# Heartmonitor_schem_EasyEDA.net
KiCad netlist of a schematic drawn in EasyEDA
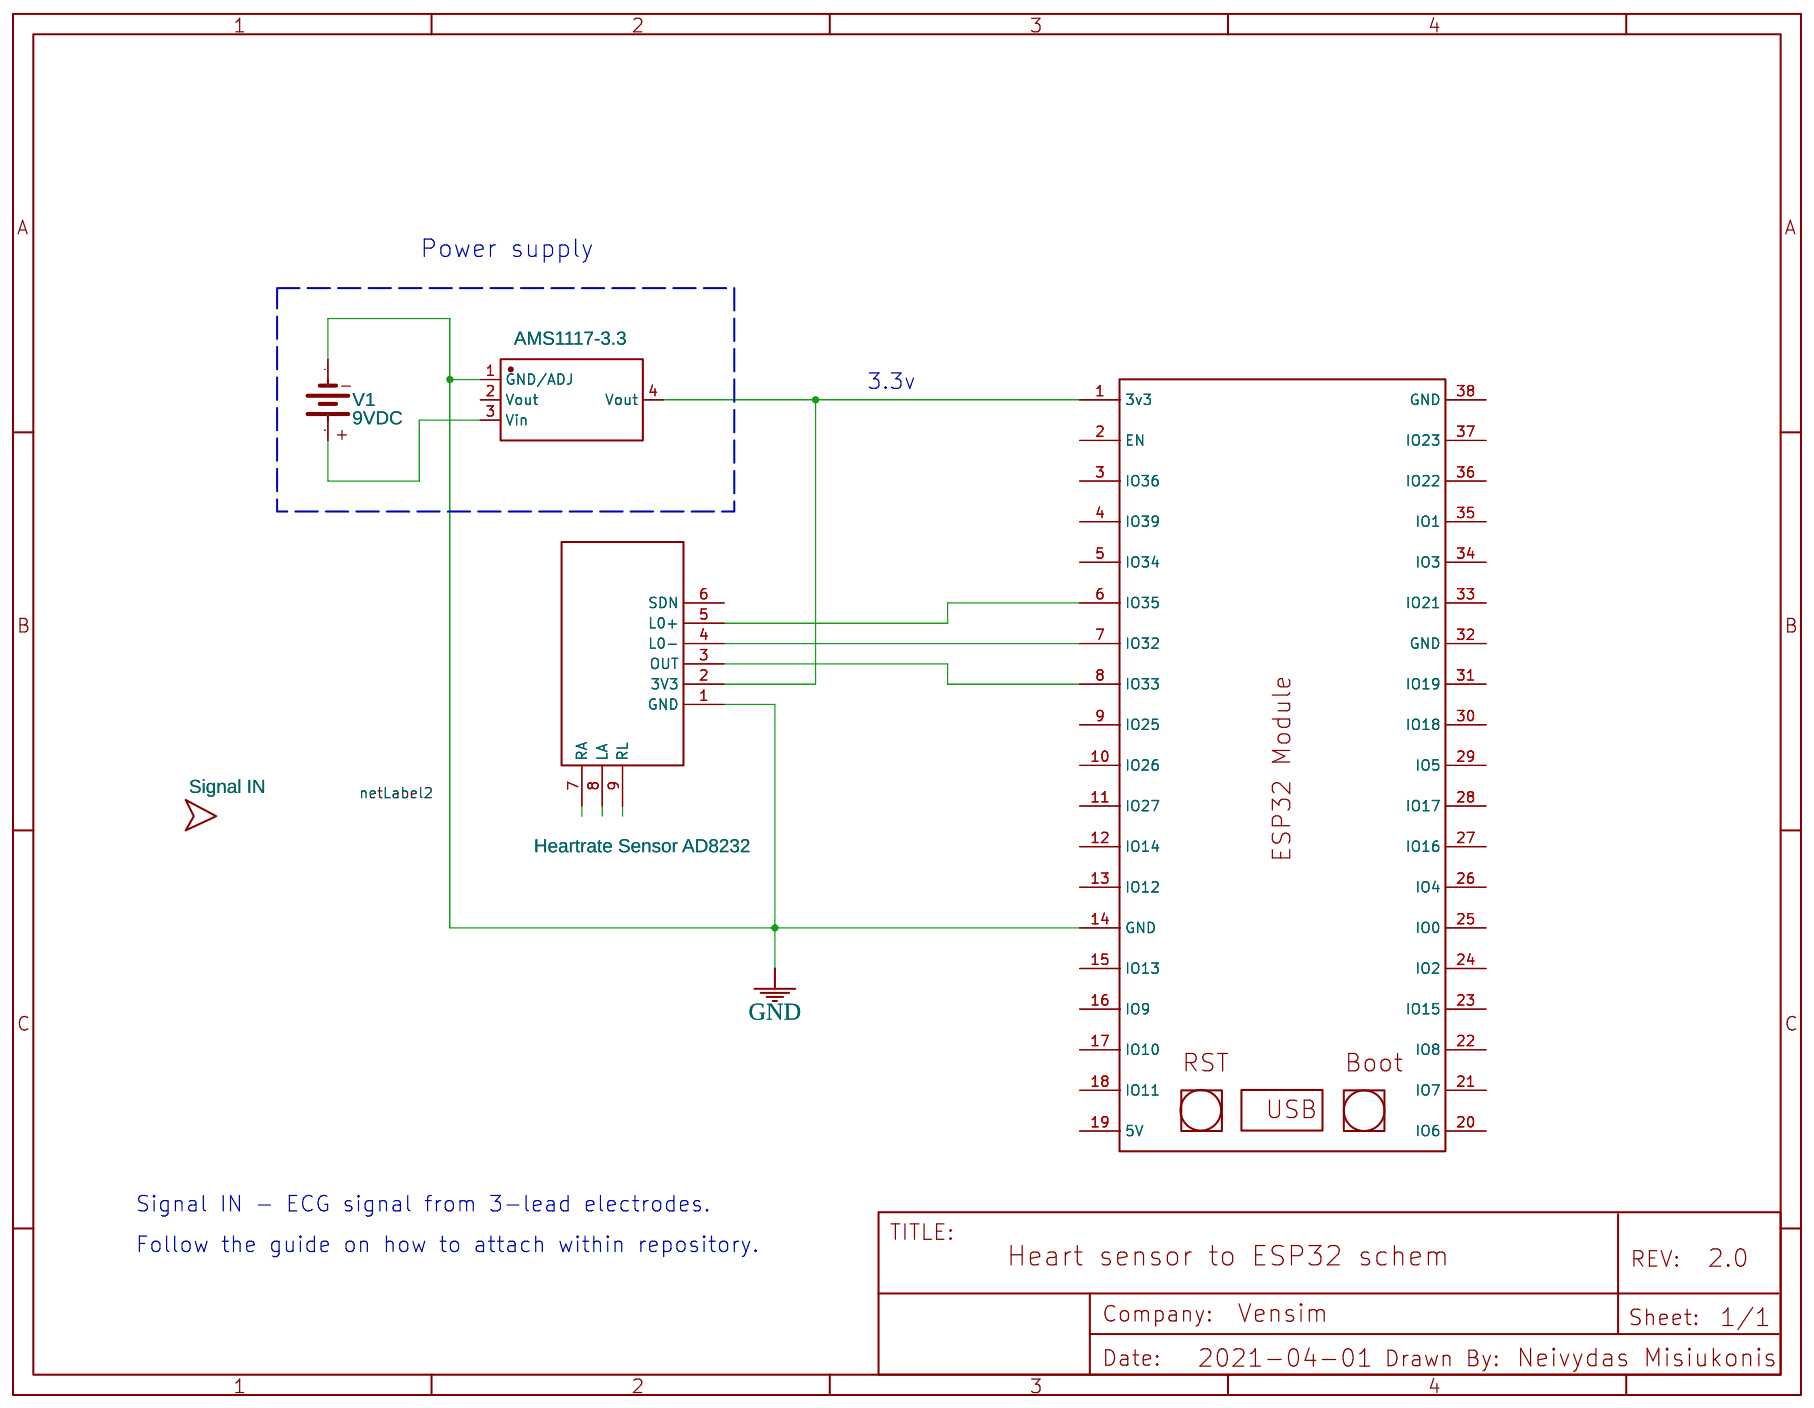
[diagram p0: schematic sheet]

(export (version "E")
  (design (tool "Eeschema 10.0.6"))
  (components
    (comp (ref "U1") (value "Heartrate Sensor AD8232") (libsource (lib "") (part "Heartrate Sensor AD8232")))
    (comp (ref "U2")
      (value "ESP32 BLADE")
      (fields (field (name "BOM_Manufacturer Part") "ESP32"))
      (libsource (lib "") (part "ESP32 BLADE"))
    )
    (comp (ref "U3")
      (value "AMS1117-3.3")
      (fields (field (name "BOM_Supplier Part") "C6186"))
      (libsource (lib "") (part "AMS1117-3.3"))
    )
    (comp (ref "U4") (value "Signal IN") (libsource (lib "") (part "Signal IN")))
    (comp (ref "V1") (value "9VDC") (libsource (lib "") (part "DC")))
  )
  (nets
    (net (code "2") (name "GND") (class "Default")
      (node (ref "U1") (pin "1") (pinfunction "GND_1") (pintype "unspecified"))
      (node (ref "U2") (pin "14") (pinfunction "GND_14") (pintype "bidirectional"))
      (node (ref "U3") (pin "1") (pinfunction "GND/ADJ_1") (pintype "unspecified"))
      (node (ref "V1") (pin "-") (pinfunction "-_-") (pintype "unspecified"))
    )
    (net (code "3") (name "Net-(U1-3V3)") (class "Default")
      (node (ref "U1") (pin "2") (pinfunction "3V3_2") (pintype "unspecified"))
      (node (ref "U2") (pin "1") (pinfunction "3v3_1") (pintype "passive"))
      (node (ref "U3") (pin "4") (pinfunction "Vout_4") (pintype "unspecified"))
    )
    (net (code "4") (name "Net-(U1-L0+)") (class "Default")
      (node (ref "U1") (pin "5") (pinfunction "L0+_5") (pintype "unspecified"))
      (node (ref "U2") (pin "6") (pinfunction "IO35_6") (pintype "bidirectional"))
    )
    (net (code "5") (name "Net-(U1-L0-)") (class "Default")
      (node (ref "U1") (pin "4") (pinfunction "L0-_4") (pintype "unspecified"))
      (node (ref "U2") (pin "7") (pinfunction "IO32_7") (pintype "bidirectional"))
    )
    (net (code "6") (name "Net-(U1-OUT)") (class "Default")
      (node (ref "U1") (pin "3") (pinfunction "OUT_3") (pintype "unspecified"))
      (node (ref "U2") (pin "8") (pinfunction "IO33_8") (pintype "unspecified"))
    )
    (net (code "7") (name "Net-(U3-Vin)") (class "Default")
      (node (ref "U3") (pin "3") (pinfunction "Vin_3") (pintype "unspecified"))
      (node (ref "V1") (pin "+") (pinfunction "+_+") (pintype "unspecified"))
    )
    (net (code "8") (name "unconnected-(U1-LA-Pad8)") (class "Default")
      (node (ref "U1") (pin "8") (pinfunction "LA_8") (pintype "unspecified"))
    )
    (net (code "9") (name "unconnected-(U1-RA-Pad7)") (class "Default")
      (node (ref "U1") (pin "7") (pinfunction "RA_7") (pintype "unspecified"))
    )
    (net (code "10") (name "unconnected-(U1-RL-Pad9)") (class "Default")
      (node (ref "U1") (pin "9") (pinfunction "RL_9") (pintype "unspecified"))
    )
    (net (code "11") (name "unconnected-(U1-SDN-Pad6)") (class "Default")
      (node (ref "U1") (pin "6") (pinfunction "SDN_6") (pintype "unspecified"))
    )
    (net (code "12") (name "unconnected-(U2-5V-Pad19)") (class "Default")
      (node (ref "U2") (pin "19") (pinfunction "5V_19") (pintype "unspecified"))
    )
    (net (code "13") (name "unconnected-(U2-EN-Pad2)") (class "Default")
      (node (ref "U2") (pin "2") (pinfunction "EN_2") (pintype "passive"))
    )
    (net (code "14") (name "unconnected-(U2-GND-Pad32)") (class "Default")
      (node (ref "U2") (pin "32") (pinfunction "GND_32") (pintype "passive"))
    )
    (net (code "15") (name "unconnected-(U2-GND-Pad38)") (class "Default")
      (node (ref "U2") (pin "38") (pinfunction "GND_38") (pintype "passive"))
    )
    (net (code "16") (name "unconnected-(U2-IO0-Pad25)") (class "Default")
      (node (ref "U2") (pin "25") (pinfunction "IO0_25") (pintype "unspecified"))
    )
    (net (code "17") (name "unconnected-(U2-IO1-Pad35)") (class "Default")
      (node (ref "U2") (pin "35") (pinfunction "IO1_35") (pintype "passive"))
    )
    (net (code "18") (name "unconnected-(U2-IO2-Pad24)") (class "Default")
      (node (ref "U2") (pin "24") (pinfunction "IO2_24") (pintype "unspecified"))
    )
    (net (code "19") (name "unconnected-(U2-IO3-Pad34)") (class "Default")
      (node (ref "U2") (pin "34") (pinfunction "IO3_34") (pintype "passive"))
    )
    (net (code "20") (name "unconnected-(U2-IO4-Pad26)") (class "Default")
      (node (ref "U2") (pin "26") (pinfunction "IO4_26") (pintype "unspecified"))
    )
    (net (code "21") (name "unconnected-(U2-IO5-Pad29)") (class "Default")
      (node (ref "U2") (pin "29") (pinfunction "IO5_29") (pintype "passive"))
    )
    (net (code "22") (name "unconnected-(U2-IO6-Pad20)") (class "Default")
      (node (ref "U2") (pin "20") (pinfunction "IO6_20") (pintype "unspecified"))
    )
    (net (code "23") (name "unconnected-(U2-IO7-Pad21)") (class "Default")
      (node (ref "U2") (pin "21") (pinfunction "IO7_21") (pintype "unspecified"))
    )
    (net (code "24") (name "unconnected-(U2-IO8-Pad22)") (class "Default")
      (node (ref "U2") (pin "22") (pinfunction "IO8_22") (pintype "unspecified"))
    )
    (net (code "25") (name "unconnected-(U2-IO9-Pad16)") (class "Default")
      (node (ref "U2") (pin "16") (pinfunction "IO9_16") (pintype "unspecified"))
    )
    (net (code "26") (name "unconnected-(U2-IO10-Pad17)") (class "Default")
      (node (ref "U2") (pin "17") (pinfunction "IO10_17") (pintype "unspecified"))
    )
    (net (code "27") (name "unconnected-(U2-IO11-Pad18)") (class "Default")
      (node (ref "U2") (pin "18") (pinfunction "IO11_18") (pintype "unspecified"))
    )
    (net (code "28") (name "unconnected-(U2-IO12-Pad13)") (class "Default")
      (node (ref "U2") (pin "13") (pinfunction "IO12_13") (pintype "bidirectional"))
    )
    (net (code "29") (name "unconnected-(U2-IO13-Pad15)") (class "Default")
      (node (ref "U2") (pin "15") (pinfunction "IO13_15") (pintype "bidirectional"))
    )
    (net (code "30") (name "unconnected-(U2-IO14-Pad12)") (class "Default")
      (node (ref "U2") (pin "12") (pinfunction "IO14_12") (pintype "bidirectional"))
    )
    (net (code "31") (name "unconnected-(U2-IO15-Pad23)") (class "Default")
      (node (ref "U2") (pin "23") (pinfunction "IO15_23") (pintype "unspecified"))
    )
    (net (code "32") (name "unconnected-(U2-IO16-Pad27)") (class "Default")
      (node (ref "U2") (pin "27") (pinfunction "IO16_27") (pintype "unspecified"))
    )
    (net (code "33") (name "unconnected-(U2-IO17-Pad28)") (class "Default")
      (node (ref "U2") (pin "28") (pinfunction "IO17_28") (pintype "bidirectional"))
    )
    (net (code "34") (name "unconnected-(U2-IO18-Pad30)") (class "Default")
      (node (ref "U2") (pin "30") (pinfunction "IO18_30") (pintype "passive"))
    )
    (net (code "35") (name "unconnected-(U2-IO19-Pad31)") (class "Default")
      (node (ref "U2") (pin "31") (pinfunction "IO19_31") (pintype "passive"))
    )
    (net (code "36") (name "unconnected-(U2-IO21-Pad33)") (class "Default")
      (node (ref "U2") (pin "33") (pinfunction "IO21_33") (pintype "passive"))
    )
    (net (code "37") (name "unconnected-(U2-IO22-Pad36)") (class "Default")
      (node (ref "U2") (pin "36") (pinfunction "IO22_36") (pintype "passive"))
    )
    (net (code "38") (name "unconnected-(U2-IO23-Pad37)") (class "Default")
      (node (ref "U2") (pin "37") (pinfunction "IO23_37") (pintype "passive"))
    )
    (net (code "39") (name "unconnected-(U2-IO25-Pad9)") (class "Default")
      (node (ref "U2") (pin "9") (pinfunction "IO25_9") (pintype "unspecified"))
    )
    (net (code "40") (name "unconnected-(U2-IO26-Pad10)") (class "Default")
      (node (ref "U2") (pin "10") (pinfunction "IO26_10") (pintype "bidirectional"))
    )
    (net (code "41") (name "unconnected-(U2-IO27-Pad11)") (class "Default")
      (node (ref "U2") (pin "11") (pinfunction "IO27_11") (pintype "bidirectional"))
    )
    (net (code "42") (name "unconnected-(U2-IO34-Pad5)") (class "Default")
      (node (ref "U2") (pin "5") (pinfunction "IO34_5") (pintype "bidirectional"))
    )
    (net (code "43") (name "unconnected-(U2-IO36-Pad3)") (class "Default")
      (node (ref "U2") (pin "3") (pinfunction "IO36_3") (pintype "bidirectional"))
    )
    (net (code "44") (name "unconnected-(U2-IO39-Pad4)") (class "Default")
      (node (ref "U2") (pin "4") (pinfunction "IO39_4") (pintype "bidirectional"))
    )
    (net (code "45") (name "unconnected-(U3-Vout-Pad2)") (class "Default")
      (node (ref "U3") (pin "2") (pinfunction "Vout_2") (pintype "unspecified"))
    )
  )
)
